# jdt1800-v0_2.net
KiCad netlist of a schematic drawn in EAGLE
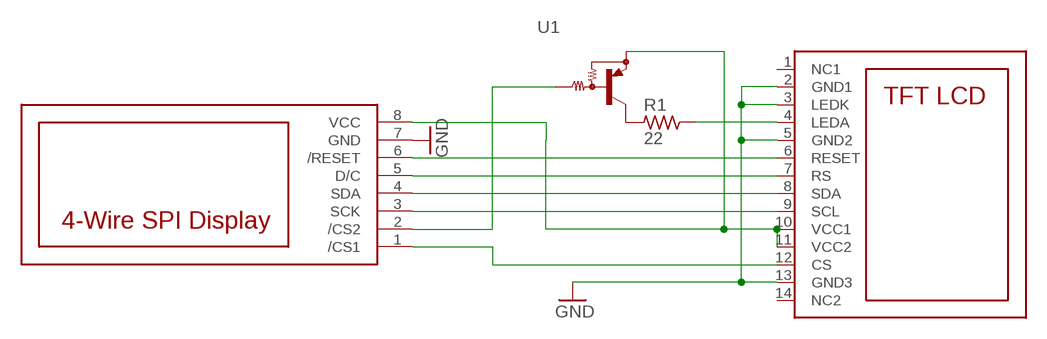
[diagram p0: schematic, sheet 1]

(export (version "E")
  (design (tool "Eeschema 10.0.6"))
  (components
    (comp (ref "R1")
      (value "22")
      (footprint "eagle-import:R0603")
      (libsource (lib "eagle-import") (part "R_0603"))
    )
    (comp (ref "U$1")
      (value "TFT1.8\"")
      (footprint "eagle-import:1.8TFT")
      (libsource (lib "eagle-import") (part "TFT1.8{dblquote}"))
    )
    (comp (ref "U$2")
      (value "4W-SPI-DISP")
      (footprint "eagle-import:1X08-NOSILK")
      (libsource (lib "eagle-import") (part "4W-SPI-DISP"))
    )
    (comp (ref "U1")
      (value "PNP-DRIVERSOT323")
      (footprint "eagle-import:SOT323R")
      (libsource (lib "eagle-import") (part "PNP-DRIVERSOT323"))
    )
  )
  (nets
    (net (code "1") (name "GND") (class "Default")
      (node (ref "U$1") (pin "13") (pinfunction "GND3_13") (pintype "bidirectional"))
      (node (ref "U$1") (pin "2") (pinfunction "GND1_2") (pintype "bidirectional"))
      (node (ref "U$1") (pin "3") (pinfunction "LEDK_3") (pintype "bidirectional"))
      (node (ref "U$1") (pin "5") (pinfunction "GND2_5") (pintype "bidirectional"))
      (node (ref "U$2") (pin "7") (pinfunction "GND_7") (pintype "power_in"))
    )
    (net (code "2") (name "Net-(U$1-CS)") (class "Default")
      (node (ref "U$1") (pin "12") (pinfunction "CS_12") (pintype "bidirectional"))
      (node (ref "U$2") (pin "1") (pinfunction "/CS1_1") (pintype "bidirectional"))
    )
    (net (code "3") (name "Net-(U$1-LEDA)") (class "Default")
      (node (ref "R1") (pin "2") (pinfunction "2_2") (pintype "passive"))
      (node (ref "U$1") (pin "4") (pinfunction "LEDA_4") (pintype "bidirectional"))
    )
    (net (code "4") (name "Net-(U$1-RESET)") (class "Default")
      (node (ref "U$1") (pin "6") (pinfunction "RESET_6") (pintype "bidirectional"))
      (node (ref "U$2") (pin "6") (pinfunction "/RESET_6") (pintype "bidirectional"))
    )
    (net (code "5") (name "Net-(U$1-RS)") (class "Default")
      (node (ref "U$1") (pin "7") (pinfunction "RS_7") (pintype "bidirectional"))
      (node (ref "U$2") (pin "5") (pinfunction "D/C_5") (pintype "bidirectional"))
    )
    (net (code "6") (name "Net-(U$1-SCL)") (class "Default")
      (node (ref "U$1") (pin "9") (pinfunction "SCL_9") (pintype "bidirectional"))
      (node (ref "U$2") (pin "3") (pinfunction "SCK_3") (pintype "bidirectional"))
    )
    (net (code "7") (name "Net-(U$1-SDA)") (class "Default")
      (node (ref "U$1") (pin "8") (pinfunction "SDA_8") (pintype "bidirectional"))
      (node (ref "U$2") (pin "4") (pinfunction "SDA_4") (pintype "bidirectional"))
    )
    (net (code "8") (name "Net-(U$1-VCC1)") (class "Default")
      (node (ref "U$1") (pin "10") (pinfunction "VCC1_10") (pintype "bidirectional"))
      (node (ref "U$1") (pin "11") (pinfunction "VCC2_11") (pintype "bidirectional"))
      (node (ref "U$2") (pin "8") (pinfunction "VCC_8") (pintype "power_in"))
      (node (ref "U1") (pin "2") (pinfunction "E_2") (pintype "passive"))
    )
    (net (code "9") (name "Net-(U$2-{slash}CS2)") (class "Default")
      (node (ref "U$2") (pin "2") (pinfunction "/CS2_2") (pintype "bidirectional"))
      (node (ref "U1") (pin "1") (pinfunction "B_1") (pintype "passive"))
    )
    (net (code "10") (name "Net-(U1-C)") (class "Default")
      (node (ref "R1") (pin "1") (pinfunction "1_1") (pintype "passive"))
      (node (ref "U1") (pin "3") (pinfunction "C_3") (pintype "passive"))
    )
    (net (code "11") (name "unconnected-(U$1-NC1-Pad1)") (class "Default")
      (node (ref "U$1") (pin "1") (pinfunction "NC1_1") (pintype "bidirectional"))
    )
    (net (code "12") (name "unconnected-(U$1-NC2-Pad14)") (class "Default")
      (node (ref "U$1") (pin "14") (pinfunction "NC2_14") (pintype "bidirectional"))
    )
  )
)
